# clock-digits.net
KiCad netlist of a schematic drawn in EAGLE
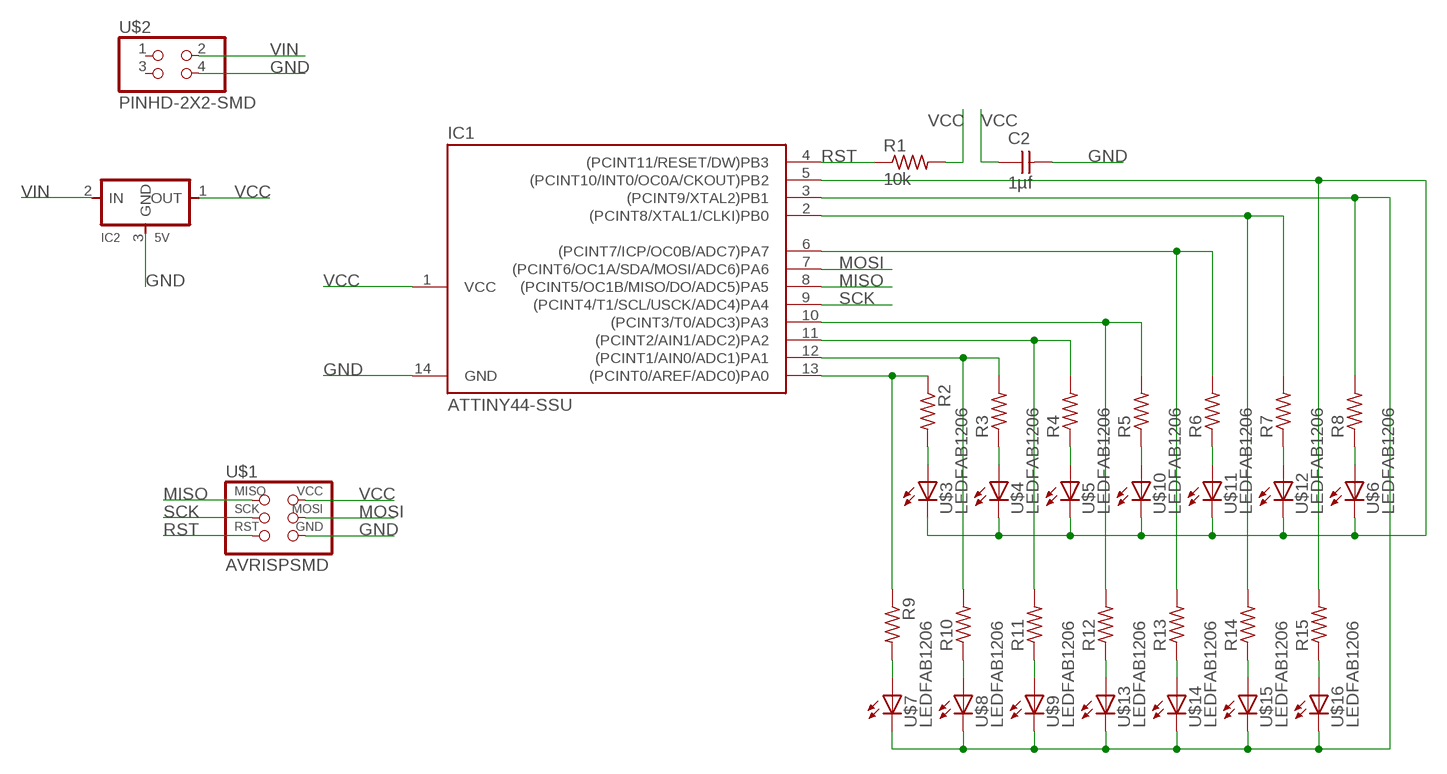
[diagram p0: schematic, sheet 1]

(export (version "E")
  (design (tool "Eeschema 10.0.6"))
  (components
    (comp (ref "C2")
      (value "1µf")
      (footprint "eagle-import:C1206FAB")
      (libsource (lib "eagle-import") (part "CAP-UNPOLARIZEDFAB"))
    )
    (comp (ref "IC1")
      (value "ATTINY44-SSU")
      (footprint "eagle-import:SOIC14")
      (libsource (lib "eagle-import") (part "ATTINY44-SSU"))
    )
    (comp (ref "IC2")
      (value "5V")
      (footprint "eagle-import:SOT23")
      (libsource (lib "eagle-import") (part "REGULATORSOT23"))
    )
    (comp (ref "R1")
      (value "10k")
      (footprint "eagle-import:R1206FAB")
      (libsource (lib "eagle-import") (part "RES-US1206FAB"))
    )
    (comp (ref "R2")
      (value "RES-US1206FAB")
      (footprint "eagle-import:R1206FAB")
      (libsource (lib "eagle-import") (part "RES-US1206FAB"))
    )
    (comp (ref "R3")
      (value "RES-US1206FAB")
      (footprint "eagle-import:R1206FAB")
      (libsource (lib "eagle-import") (part "RES-US1206FAB"))
    )
    (comp (ref "R4")
      (value "RES-US1206FAB")
      (footprint "eagle-import:R1206FAB")
      (libsource (lib "eagle-import") (part "RES-US1206FAB"))
    )
    (comp (ref "R5")
      (value "RES-US1206FAB")
      (footprint "eagle-import:R1206FAB")
      (libsource (lib "eagle-import") (part "RES-US1206FAB"))
    )
    (comp (ref "R6")
      (value "RES-US1206FAB")
      (footprint "eagle-import:R1206FAB")
      (libsource (lib "eagle-import") (part "RES-US1206FAB"))
    )
    (comp (ref "R7")
      (value "RES-US1206FAB")
      (footprint "eagle-import:R1206FAB")
      (libsource (lib "eagle-import") (part "RES-US1206FAB"))
    )
    (comp (ref "R8")
      (value "RES-US1206FAB")
      (footprint "eagle-import:R1206FAB")
      (libsource (lib "eagle-import") (part "RES-US1206FAB"))
    )
    (comp (ref "R9")
      (value "RES-US1206FAB")
      (footprint "eagle-import:R1206FAB")
      (libsource (lib "eagle-import") (part "RES-US1206FAB"))
    )
    (comp (ref "R10")
      (value "RES-US1206FAB")
      (footprint "eagle-import:R1206FAB")
      (libsource (lib "eagle-import") (part "RES-US1206FAB"))
    )
    (comp (ref "R11")
      (value "RES-US1206FAB")
      (footprint "eagle-import:R1206FAB")
      (libsource (lib "eagle-import") (part "RES-US1206FAB"))
    )
    (comp (ref "R12")
      (value "RES-US1206FAB")
      (footprint "eagle-import:R1206FAB")
      (libsource (lib "eagle-import") (part "RES-US1206FAB"))
    )
    (comp (ref "R13")
      (value "RES-US1206FAB")
      (footprint "eagle-import:R1206FAB")
      (libsource (lib "eagle-import") (part "RES-US1206FAB"))
    )
    (comp (ref "R14")
      (value "RES-US1206FAB")
      (footprint "eagle-import:R1206FAB")
      (libsource (lib "eagle-import") (part "RES-US1206FAB"))
    )
    (comp (ref "R15")
      (value "RES-US1206FAB")
      (footprint "eagle-import:R1206FAB")
      (libsource (lib "eagle-import") (part "RES-US1206FAB"))
    )
    (comp (ref "U$1")
      (value "AVRISPSMD")
      (footprint "eagle-import:2X03SMD")
      (libsource (lib "eagle-import") (part "AVRISPSMD"))
    )
    (comp (ref "U$2")
      (value "PINHD-2X2-SMD")
      (footprint "eagle-import:2X02SMD")
      (libsource (lib "eagle-import") (part "PINHD-2X2-SMD"))
    )
    (comp (ref "U$3")
      (value "LEDFAB1206")
      (footprint "eagle-import:LED1206FAB")
      (libsource (lib "eagle-import") (part "LEDFAB1206"))
    )
    (comp (ref "U$4")
      (value "LEDFAB1206")
      (footprint "eagle-import:LED1206FAB")
      (libsource (lib "eagle-import") (part "LEDFAB1206"))
    )
    (comp (ref "U$5")
      (value "LEDFAB1206")
      (footprint "eagle-import:LED1206FAB")
      (libsource (lib "eagle-import") (part "LEDFAB1206"))
    )
    (comp (ref "U$6")
      (value "LEDFAB1206")
      (footprint "eagle-import:LED1206FAB")
      (libsource (lib "eagle-import") (part "LEDFAB1206"))
    )
    (comp (ref "U$7")
      (value "LEDFAB1206")
      (footprint "eagle-import:LED1206FAB")
      (libsource (lib "eagle-import") (part "LEDFAB1206"))
    )
    (comp (ref "U$8")
      (value "LEDFAB1206")
      (footprint "eagle-import:LED1206FAB")
      (libsource (lib "eagle-import") (part "LEDFAB1206"))
    )
    (comp (ref "U$9")
      (value "LEDFAB1206")
      (footprint "eagle-import:LED1206FAB")
      (libsource (lib "eagle-import") (part "LEDFAB1206"))
    )
    (comp (ref "U$10")
      (value "LEDFAB1206")
      (footprint "eagle-import:LED1206FAB")
      (libsource (lib "eagle-import") (part "LEDFAB1206"))
    )
    (comp (ref "U$11")
      (value "LEDFAB1206")
      (footprint "eagle-import:LED1206FAB")
      (libsource (lib "eagle-import") (part "LEDFAB1206"))
    )
    (comp (ref "U$12")
      (value "LEDFAB1206")
      (footprint "eagle-import:LED1206FAB")
      (libsource (lib "eagle-import") (part "LEDFAB1206"))
    )
    (comp (ref "U$13")
      (value "LEDFAB1206")
      (footprint "eagle-import:LED1206FAB")
      (libsource (lib "eagle-import") (part "LEDFAB1206"))
    )
    (comp (ref "U$14")
      (value "LEDFAB1206")
      (footprint "eagle-import:LED1206FAB")
      (libsource (lib "eagle-import") (part "LEDFAB1206"))
    )
    (comp (ref "U$15")
      (value "LEDFAB1206")
      (footprint "eagle-import:LED1206FAB")
      (libsource (lib "eagle-import") (part "LEDFAB1206"))
    )
    (comp (ref "U$16")
      (value "LEDFAB1206")
      (footprint "eagle-import:LED1206FAB")
      (libsource (lib "eagle-import") (part "LEDFAB1206"))
    )
  )
  (nets
    (net (code "1") (name "/GND") (class "Default")
      (node (ref "C2") (pin "2") (pinfunction "2_2") (pintype "passive"))
      (node (ref "IC1") (pin "14") (pinfunction "GND_14") (pintype "power_in"))
      (node (ref "IC2") (pin "3") (pinfunction "GND_3") (pintype "bidirectional"))
      (node (ref "U$1") (pin "6") (pinfunction "GND_6") (pintype "passive"))
      (node (ref "U$2") (pin "4") (pinfunction "4_4") (pintype "passive"))
    )
    (net (code "2") (name "/MISO") (class "Default")
      (node (ref "IC1") (pin "8") (pinfunction "(PCINT5/OC1B/MISO/DO/ADC5)PA5_8") (pintype "bidirectional"))
      (node (ref "U$1") (pin "1") (pinfunction "MISO_1") (pintype "passive"))
    )
    (net (code "3") (name "/MOSI") (class "Default")
      (node (ref "IC1") (pin "7") (pinfunction "(PCINT6/OC1A/SDA/MOSI/ADC6)PA6_7") (pintype "bidirectional"))
      (node (ref "U$1") (pin "4") (pinfunction "MOSI_4") (pintype "passive"))
    )
    (net (code "4") (name "/RST") (class "Default")
      (node (ref "IC1") (pin "4") (pinfunction "(PCINT11/RESET/DW)PB3_4") (pintype "bidirectional"))
      (node (ref "R1") (pin "1") (pinfunction "1_1") (pintype "passive"))
      (node (ref "U$1") (pin "5") (pinfunction "RST_5") (pintype "passive"))
    )
    (net (code "5") (name "/SCK") (class "Default")
      (node (ref "IC1") (pin "9") (pinfunction "(PCINT4/T1/SCL/USCK/ADC4)PA4_9") (pintype "bidirectional"))
      (node (ref "U$1") (pin "3") (pinfunction "SCK_3") (pintype "passive"))
    )
    (net (code "6") (name "/VCC") (class "Default")
      (node (ref "C2") (pin "1") (pinfunction "1_1") (pintype "passive"))
      (node (ref "IC1") (pin "1") (pinfunction "VCC_1") (pintype "power_in"))
      (node (ref "IC2") (pin "1") (pinfunction "OUT_1") (pintype "bidirectional"))
      (node (ref "R1") (pin "2") (pinfunction "2_2") (pintype "passive"))
      (node (ref "U$1") (pin "2") (pinfunction "VCC_2") (pintype "passive"))
    )
    (net (code "7") (name "/VIN") (class "Default")
      (node (ref "IC2") (pin "2") (pinfunction "IN_2") (pintype "bidirectional"))
      (node (ref "U$2") (pin "2") (pinfunction "2_2") (pintype "passive"))
    )
    (net (code "8") (name "Net-(IC1-(PCINT0{slash}AREF{slash}ADC0)PA0)") (class "Default")
      (node (ref "IC1") (pin "13") (pinfunction "(PCINT0/AREF/ADC0)PA0_13") (pintype "bidirectional"))
      (node (ref "R2") (pin "1") (pinfunction "1_1") (pintype "passive"))
      (node (ref "R9") (pin "1") (pinfunction "1_1") (pintype "passive"))
    )
    (net (code "9") (name "Net-(IC1-(PCINT1{slash}AIN0{slash}ADC1)PA1)") (class "Default")
      (node (ref "IC1") (pin "12") (pinfunction "(PCINT1/AIN0/ADC1)PA1_12") (pintype "bidirectional"))
      (node (ref "R10") (pin "2") (pinfunction "2_2") (pintype "passive"))
      (node (ref "R3") (pin "2") (pinfunction "2_2") (pintype "passive"))
    )
    (net (code "10") (name "Net-(IC1-(PCINT2{slash}AIN1{slash}ADC2)PA2)") (class "Default")
      (node (ref "IC1") (pin "11") (pinfunction "(PCINT2/AIN1/ADC2)PA2_11") (pintype "bidirectional"))
      (node (ref "R11") (pin "2") (pinfunction "2_2") (pintype "passive"))
      (node (ref "R4") (pin "2") (pinfunction "2_2") (pintype "passive"))
    )
    (net (code "11") (name "Net-(IC1-(PCINT3{slash}T0{slash}ADC3)PA3)") (class "Default")
      (node (ref "IC1") (pin "10") (pinfunction "(PCINT3/T0/ADC3)PA3_10") (pintype "bidirectional"))
      (node (ref "R12") (pin "2") (pinfunction "2_2") (pintype "passive"))
      (node (ref "R5") (pin "2") (pinfunction "2_2") (pintype "passive"))
    )
    (net (code "12") (name "Net-(IC1-(PCINT7{slash}ICP{slash}OC0B{slash}ADC7)PA7)") (class "Default")
      (node (ref "IC1") (pin "6") (pinfunction "(PCINT7/ICP/OC0B/ADC7)PA7_6") (pintype "bidirectional"))
      (node (ref "R13") (pin "2") (pinfunction "2_2") (pintype "passive"))
      (node (ref "R6") (pin "2") (pinfunction "2_2") (pintype "passive"))
    )
    (net (code "13") (name "Net-(IC1-(PCINT8{slash}XTAL1{slash}CLKI)PB0)") (class "Default")
      (node (ref "IC1") (pin "2") (pinfunction "(PCINT8/XTAL1/CLKI)PB0_2") (pintype "bidirectional"))
      (node (ref "R14") (pin "2") (pinfunction "2_2") (pintype "passive"))
      (node (ref "R7") (pin "2") (pinfunction "2_2") (pintype "passive"))
    )
    (net (code "14") (name "Net-(IC1-(PCINT9{slash}XTAL2)PB1)") (class "Default")
      (node (ref "IC1") (pin "3") (pinfunction "(PCINT9/XTAL2)PB1_3") (pintype "bidirectional"))
      (node (ref "R8") (pin "2") (pinfunction "2_2") (pintype "passive"))
      (node (ref "U$13") (pin "2") (pinfunction "C_2") (pintype "passive"))
      (node (ref "U$14") (pin "2") (pinfunction "C_2") (pintype "passive"))
      (node (ref "U$15") (pin "2") (pinfunction "C_2") (pintype "passive"))
      (node (ref "U$16") (pin "2") (pinfunction "C_2") (pintype "passive"))
      (node (ref "U$7") (pin "2") (pinfunction "C_2") (pintype "passive"))
      (node (ref "U$8") (pin "2") (pinfunction "C_2") (pintype "passive"))
      (node (ref "U$9") (pin "2") (pinfunction "C_2") (pintype "passive"))
    )
    (net (code "15") (name "Net-(IC1-(PCINT10{slash}INT0{slash}OC0A{slash}CKOUT)PB2)") (class "Default")
      (node (ref "IC1") (pin "5") (pinfunction "(PCINT10/INT0/OC0A/CKOUT)PB2_5") (pintype "bidirectional"))
      (node (ref "R15") (pin "2") (pinfunction "2_2") (pintype "passive"))
      (node (ref "U$10") (pin "2") (pinfunction "C_2") (pintype "passive"))
      (node (ref "U$11") (pin "2") (pinfunction "C_2") (pintype "passive"))
      (node (ref "U$12") (pin "2") (pinfunction "C_2") (pintype "passive"))
      (node (ref "U$3") (pin "2") (pinfunction "C_2") (pintype "passive"))
      (node (ref "U$4") (pin "2") (pinfunction "C_2") (pintype "passive"))
      (node (ref "U$5") (pin "2") (pinfunction "C_2") (pintype "passive"))
      (node (ref "U$6") (pin "2") (pinfunction "C_2") (pintype "passive"))
    )
    (net (code "16") (name "Net-(U$3-A)") (class "Default")
      (node (ref "R2") (pin "2") (pinfunction "2_2") (pintype "passive"))
      (node (ref "U$3") (pin "1") (pinfunction "A_1") (pintype "passive"))
    )
    (net (code "17") (name "Net-(U$4-A)") (class "Default")
      (node (ref "R3") (pin "1") (pinfunction "1_1") (pintype "passive"))
      (node (ref "U$4") (pin "1") (pinfunction "A_1") (pintype "passive"))
    )
    (net (code "18") (name "Net-(U$5-A)") (class "Default")
      (node (ref "R4") (pin "1") (pinfunction "1_1") (pintype "passive"))
      (node (ref "U$5") (pin "1") (pinfunction "A_1") (pintype "passive"))
    )
    (net (code "19") (name "Net-(U$6-A)") (class "Default")
      (node (ref "R8") (pin "1") (pinfunction "1_1") (pintype "passive"))
      (node (ref "U$6") (pin "1") (pinfunction "A_1") (pintype "passive"))
    )
    (net (code "20") (name "Net-(U$7-A)") (class "Default")
      (node (ref "R9") (pin "2") (pinfunction "2_2") (pintype "passive"))
      (node (ref "U$7") (pin "1") (pinfunction "A_1") (pintype "passive"))
    )
    (net (code "21") (name "Net-(U$8-A)") (class "Default")
      (node (ref "R10") (pin "1") (pinfunction "1_1") (pintype "passive"))
      (node (ref "U$8") (pin "1") (pinfunction "A_1") (pintype "passive"))
    )
    (net (code "22") (name "Net-(U$9-A)") (class "Default")
      (node (ref "R11") (pin "1") (pinfunction "1_1") (pintype "passive"))
      (node (ref "U$9") (pin "1") (pinfunction "A_1") (pintype "passive"))
    )
    (net (code "23") (name "Net-(U$10-A)") (class "Default")
      (node (ref "R5") (pin "1") (pinfunction "1_1") (pintype "passive"))
      (node (ref "U$10") (pin "1") (pinfunction "A_1") (pintype "passive"))
    )
    (net (code "24") (name "Net-(U$11-A)") (class "Default")
      (node (ref "R6") (pin "1") (pinfunction "1_1") (pintype "passive"))
      (node (ref "U$11") (pin "1") (pinfunction "A_1") (pintype "passive"))
    )
    (net (code "25") (name "Net-(U$12-A)") (class "Default")
      (node (ref "R7") (pin "1") (pinfunction "1_1") (pintype "passive"))
      (node (ref "U$12") (pin "1") (pinfunction "A_1") (pintype "passive"))
    )
    (net (code "26") (name "Net-(U$13-A)") (class "Default")
      (node (ref "R12") (pin "1") (pinfunction "1_1") (pintype "passive"))
      (node (ref "U$13") (pin "1") (pinfunction "A_1") (pintype "passive"))
    )
    (net (code "27") (name "Net-(U$14-A)") (class "Default")
      (node (ref "R13") (pin "1") (pinfunction "1_1") (pintype "passive"))
      (node (ref "U$14") (pin "1") (pinfunction "A_1") (pintype "passive"))
    )
    (net (code "28") (name "Net-(U$15-A)") (class "Default")
      (node (ref "R14") (pin "1") (pinfunction "1_1") (pintype "passive"))
      (node (ref "U$15") (pin "1") (pinfunction "A_1") (pintype "passive"))
    )
    (net (code "29") (name "Net-(U$16-A)") (class "Default")
      (node (ref "R15") (pin "1") (pinfunction "1_1") (pintype "passive"))
      (node (ref "U$16") (pin "1") (pinfunction "A_1") (pintype "passive"))
    )
    (net (code "30") (name "unconnected-(U$2-Pad1)") (class "Default")
      (node (ref "U$2") (pin "1") (pinfunction "1_1") (pintype "passive"))
    )
    (net (code "31") (name "unconnected-(U$2-Pad3)") (class "Default")
      (node (ref "U$2") (pin "3") (pinfunction "3_3") (pintype "passive"))
    )
  )
)
